# Isolation.net
KiCad netlist of a schematic drawn in Altium Designer
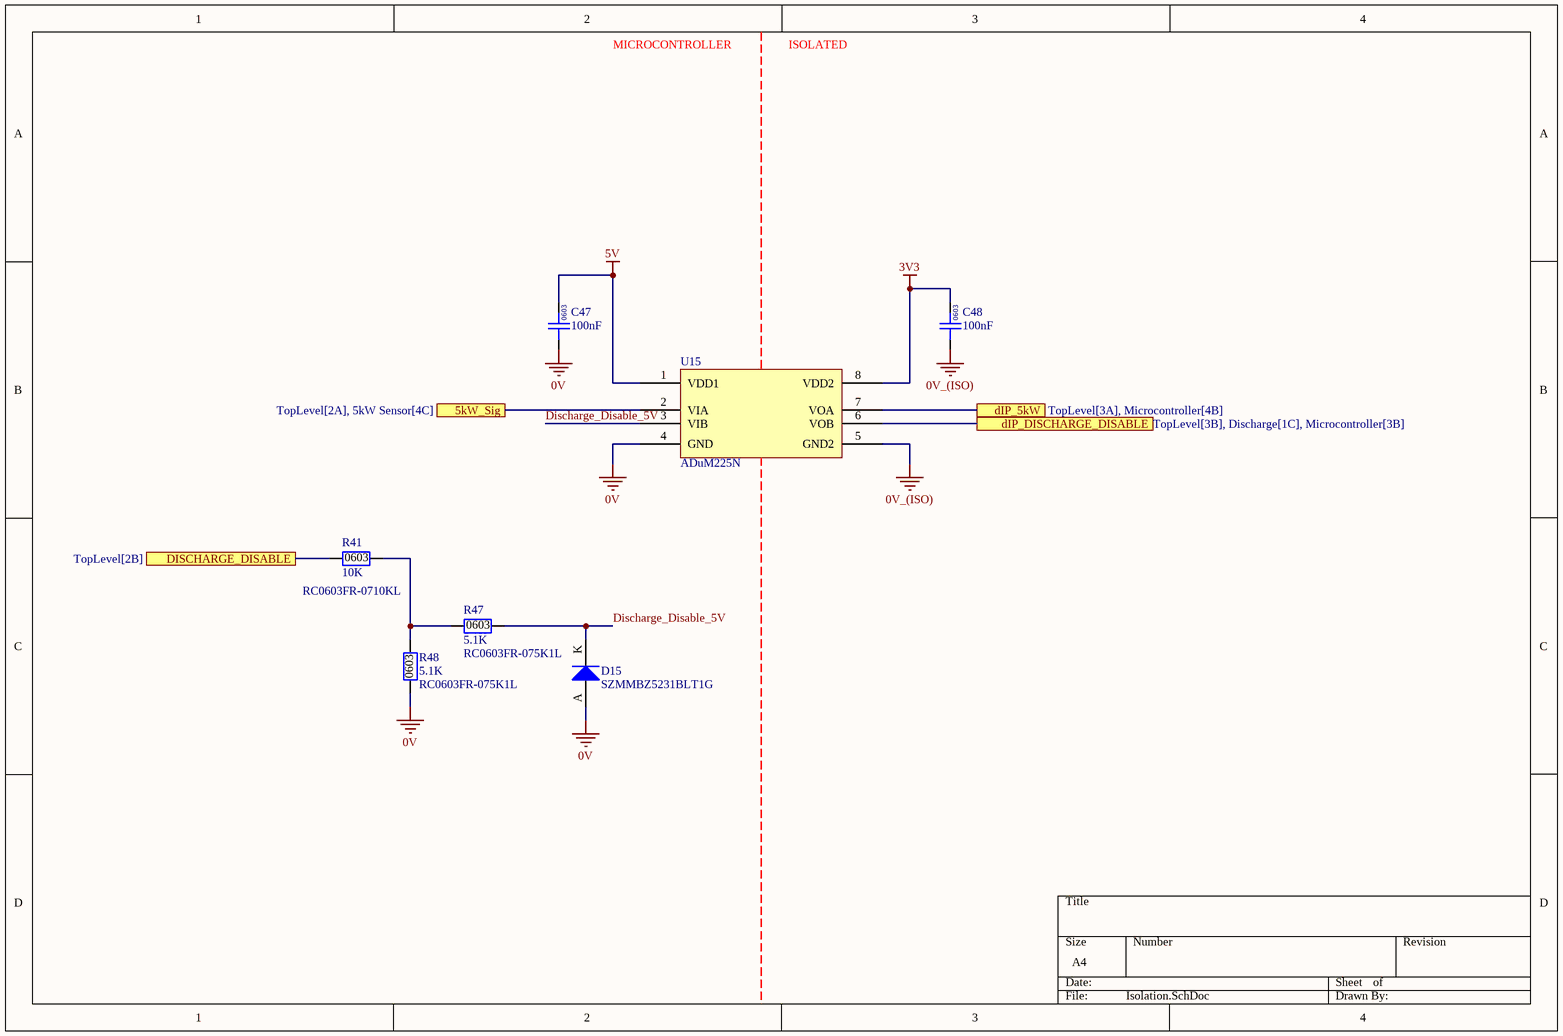
[diagram p0: Isolation.SchDoc]

(export (version "E")
  (design (tool "Eeschema 10.0.6"))
  (components
    (comp (ref "C47")
      (value "100nF")
      (footprint "0603")
      (fields
        (field (name "PART NUMBER") "GCM188L81H104KA57D")
        (field (name "MANUFACTURER") "muRata")
        (field (name "TOLERANCE") "±10%")
      )
      (libsource (lib "ts_standard_library") (part "Capacitor 0603"))
    )
    (comp (ref "C48")
      (value "100nF")
      (footprint "0603")
      (fields
        (field (name "PART NUMBER") "GCM188L81H104KA57D")
        (field (name "MANUFACTURER") "muRata")
        (field (name "TOLERANCE") "±10%")
      )
      (libsource (lib "ts_standard_library") (part "Capacitor 0603"))
    )
    (comp (ref "D15")
      (value "SZMMBZ5231BLT1G")
      (footprint "SOT23-3")
      (description "Zener Diode, 5.1V V(Z), 5.1%, 0.225W, Silicon, Unidirectional, TO-236AB")
      (fields (field (name "PART NUMBER") "BAS21"))
      (libsource (lib "Team Swinburne") (part "Diode"))
    )
    (comp (ref "R41")
      (value "RC0603FR-0710KL")
      (footprint "RESC0603")
      (description "RES SMD 10K OHM JUMPER 1/10W 0603")
      (fields (field (name "ALTIUM_VALUE") "10K") (field (name "TOLERANCE") "1%"))
      (libsource (lib "Team Swinburne") (part "Resistor"))
    )
    (comp (ref "R47")
      (value "RC0603FR-075K1L")
      (footprint "RESC0603")
      (description "RES SMD 5.1K OHM JUMPER 1/10W 0603")
      (fields (field (name "ALTIUM_VALUE") "5.1K") (field (name "TOLERANCE") "1%"))
      (libsource (lib "Team Swinburne") (part "Resistor"))
    )
    (comp (ref "R48")
      (value "RC0603FR-075K1L")
      (footprint "RESC0603")
      (description "RES SMD 5.1K OHM JUMPER 1/10W 0603")
      (fields (field (name "ALTIUM_VALUE") "5.1K") (field (name "TOLERANCE") "1%"))
      (libsource (lib "Team Swinburne") (part "Resistor"))
    )
    (comp (ref "U15")
      (value "ADuM225N")
      (footprint "AD-SOIC-8W")
      (description "DIGITAL ISOLATOR, DUAL CHANNEL")
      (fields (field (name "MANUFACTURER") "Analogue Devices"))
      (libsource (lib "ts_standard_library") (part "ADuM225N"))
    )
  )
  (nets
    (net (code "1") (name "/5kW_Sig") (class "Default")
      (node (ref "U15") (pin "2") (pinfunction "VIA_2") (pintype "passive"))
    )
    (net (code "2") (name "/DISCHARGE_DISABLE") (class "Default")
      (node (ref "R41") (pin "1") (pinfunction "1_1") (pintype "passive"))
    )
    (net (code "3") (name "/Discharge_Disable_5V") (class "Default")
      (node (ref "D15") (pin "K") (pinfunction "K_K") (pintype "passive"))
      (node (ref "R47") (pin "2") (pinfunction "2_2") (pintype "passive"))
      (node (ref "U15") (pin "3") (pinfunction "VIB_3") (pintype "passive"))
    )
    (net (code "4") (name "/dIP_5kW") (class "Default")
      (node (ref "U15") (pin "7") (pinfunction "VOA_7") (pintype "passive"))
    )
    (net (code "5") (name "/dIP_DISCHARGE_DISABLE") (class "Default")
      (node (ref "U15") (pin "6") (pinfunction "VOB_6") (pintype "passive"))
    )
    (net (code "6") (name "0V") (class "Default")
      (node (ref "C47") (pin "1") (pinfunction "1_1") (pintype "passive"))
      (node (ref "D15") (pin "A") (pinfunction "A_A") (pintype "passive"))
      (node (ref "R48") (pin "1") (pinfunction "1_1") (pintype "passive"))
      (node (ref "U15") (pin "4") (pinfunction "GND_4") (pintype "passive"))
    )
    (net (code "7") (name "0V_(ISO)") (class "Default")
      (node (ref "C48") (pin "1") (pinfunction "1_1") (pintype "passive"))
      (node (ref "U15") (pin "5") (pinfunction "GND2_5") (pintype "passive"))
    )
    (net (code "8") (name "3V3") (class "Default")
      (node (ref "C48") (pin "2") (pinfunction "2_2") (pintype "passive"))
      (node (ref "U15") (pin "8") (pinfunction "VDD2_8") (pintype "passive"))
    )
    (net (code "9") (name "5V") (class "Default")
      (node (ref "C47") (pin "2") (pinfunction "2_2") (pintype "passive"))
      (node (ref "U15") (pin "1") (pinfunction "VDD1_1") (pintype "passive"))
    )
    (net (code "10") (name "Net-(R41-Pad2)") (class "Default")
      (node (ref "R41") (pin "2") (pinfunction "2_2") (pintype "passive"))
      (node (ref "R47") (pin "1") (pinfunction "1_1") (pintype "passive"))
      (node (ref "R48") (pin "2") (pinfunction "2_2") (pintype "passive"))
    )
  )
)
